# Carrier_v1_0.net
KiCad netlist of a schematic drawn in EAGLE
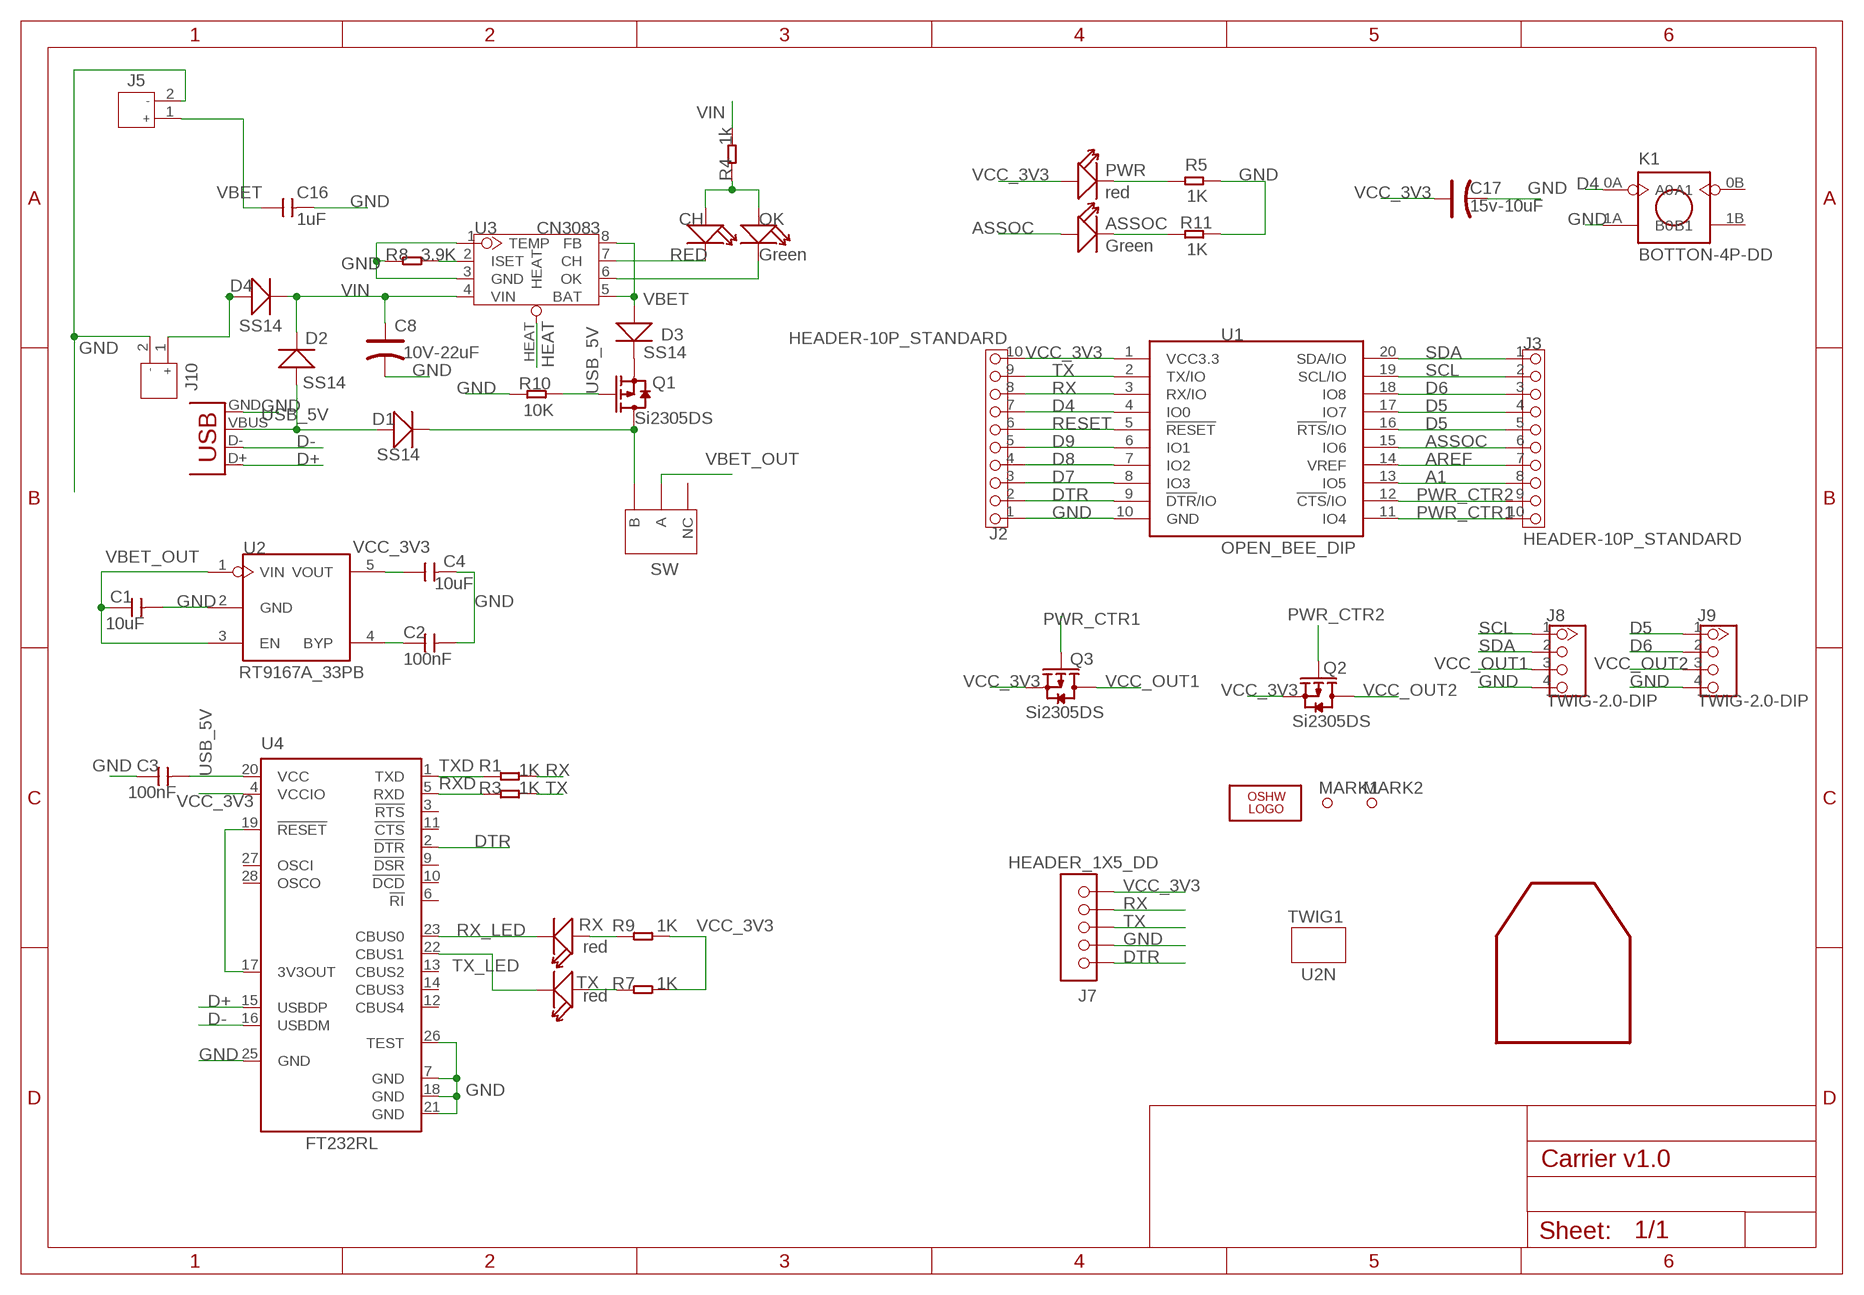
[diagram p0: schematic, sheet 1]

(export (version "E")
  (design (tool "Eeschema 10.0.6"))
  (components
    (comp (ref "ASSOC")
      (value "Green")
      (footprint "eagle-import:D0603")
      (libsource (lib "eagle-import") (part "LED-0603"))
    )
    (comp (ref "C1")
      (value "10uF")
      (footprint "eagle-import:0805")
      (libsource (lib "eagle-import") (part "C-0805"))
    )
    (comp (ref "C2")
      (value "100nF")
      (footprint "eagle-import:0603")
      (libsource (lib "eagle-import") (part "C-0603"))
    )
    (comp (ref "C3")
      (value "100nF")
      (footprint "eagle-import:0603")
      (libsource (lib "eagle-import") (part "C-0603"))
    )
    (comp (ref "C4")
      (value "10uF")
      (footprint "eagle-import:0805")
      (libsource (lib "eagle-import") (part "C-0805"))
    )
    (comp (ref "C8")
      (value "10V-22uF")
      (footprint "eagle-import:AVX-B")
      (libsource (lib "eagle-import") (part "CAP_AVX_B"))
    )
    (comp (ref "C16")
      (value "1uF")
      (footprint "eagle-import:0805")
      (libsource (lib "eagle-import") (part "C-0805"))
    )
    (comp (ref "C17")
      (value "15v-10uF")
      (footprint "eagle-import:AVX-A")
      (libsource (lib "eagle-import") (part "CAP_AVX_A"))
    )
    (comp (ref "CH")
      (value "RED")
      (footprint "eagle-import:D0603")
      (libsource (lib "eagle-import") (part "LED-0603"))
    )
    (comp (ref "D1")
      (value "SS14")
      (footprint "eagle-import:D2010")
      (libsource (lib "eagle-import") (part "D-2010"))
    )
    (comp (ref "D2")
      (value "SS14")
      (footprint "eagle-import:D2010")
      (libsource (lib "eagle-import") (part "D-2010"))
    )
    (comp (ref "D3")
      (value "SS14")
      (footprint "eagle-import:D2010")
      (libsource (lib "eagle-import") (part "D-2010"))
    )
    (comp (ref "D4")
      (value "SS14")
      (footprint "eagle-import:D2010")
      (libsource (lib "eagle-import") (part "D-2010"))
    )
    (comp (ref "J2")
      (value "HEADER-10P_STANDARD")
      (footprint "eagle-import:2.54_10P")
      (libsource (lib "eagle-import") (part "HEADER-10P_STANDARD"))
    )
    (comp (ref "J3")
      (value "HEADER-10P_STANDARD")
      (footprint "eagle-import:2.54_10P")
      (libsource (lib "eagle-import") (part "HEADER-10P_STANDARD"))
    )
    (comp (ref "J5")
      (value "JST-2P-POWER-LEADED")
      (footprint "eagle-import:2P-2.0-LEADED-4.7X6.0")
      (libsource (lib "eagle-import") (part "JST-2P-POWER-LEADED"))
    )
    (comp (ref "J7")
      (value "HEADER_1X5_DD")
      (footprint "eagle-import:CK_1X5")
      (libsource (lib "eagle-import") (part "HEADER_1X5_DD"))
    )
    (comp (ref "J8")
      (value "TWIG-2.0-DIP")
      (footprint "eagle-import:2.0_1X4")
      (libsource (lib "eagle-import") (part "TWIG-2.0-DIP"))
    )
    (comp (ref "J9")
      (value "TWIG-2.0-DIP")
      (footprint "eagle-import:2.0_1X4")
      (libsource (lib "eagle-import") (part "TWIG-2.0-DIP"))
    )
    (comp (ref "J10")
      (value "JST-2P-POWER-LEADED")
      (footprint "eagle-import:2P-2.0-LEADED-4.7X6.0")
      (libsource (lib "eagle-import") (part "JST-2P-POWER-LEADED"))
    )
    (comp (ref "K1")
      (value "BOTTON-4P-DD")
      (footprint "eagle-import:BTN-S")
      (libsource (lib "eagle-import") (part "BOTTON-4P-DD"))
    )
    (comp (ref "LOGO2")
      (value "OSHW_LOGO_FILLX0200-NT")
      (footprint "eagle-import:OSHW_FILLX200_NOTEXT")
      (libsource (lib "eagle-import") (part "OSHW_LOGO_FILLX0200-NT"))
    )
    (comp (ref "MARK1")
      (value "PAD-MARK")
      (footprint "eagle-import:MARK")
      (libsource (lib "eagle-import") (part "PAD-MARK"))
    )
    (comp (ref "MARK2")
      (value "PAD-MARK")
      (footprint "eagle-import:MARK")
      (libsource (lib "eagle-import") (part "PAD-MARK"))
    )
    (comp (ref "OK")
      (value "Green")
      (footprint "eagle-import:D0603")
      (libsource (lib "eagle-import") (part "LED-0603"))
    )
    (comp (ref "PWR")
      (value "red")
      (footprint "eagle-import:D0805")
      (libsource (lib "eagle-import") (part "LED-0805"))
    )
    (comp (ref "Q1")
      (value "Si2305DS")
      (footprint "eagle-import:SOT23")
      (libsource (lib "eagle-import") (part "010-P-MOSFETSOT23"))
    )
    (comp (ref "Q2")
      (value "Si2305DS")
      (footprint "eagle-import:SOT23")
      (libsource (lib "eagle-import") (part "010-P-MOSFETSOT23"))
    )
    (comp (ref "Q3")
      (value "Si2305DS")
      (footprint "eagle-import:SOT23")
      (libsource (lib "eagle-import") (part "010-P-MOSFETSOT23"))
    )
    (comp (ref "R1")
      (value "1K")
      (footprint "eagle-import:0603")
      (libsource (lib "eagle-import") (part "R-0603"))
    )
    (comp (ref "R3")
      (value "1K")
      (footprint "eagle-import:0603")
      (libsource (lib "eagle-import") (part "R-0603"))
    )
    (comp (ref "R4")
      (value "1k")
      (footprint "eagle-import:0603")
      (libsource (lib "eagle-import") (part "R-0603"))
    )
    (comp (ref "R5")
      (value "1K")
      (footprint "eagle-import:0603")
      (libsource (lib "eagle-import") (part "R-0603"))
    )
    (comp (ref "R7")
      (value "1K")
      (footprint "eagle-import:0603")
      (libsource (lib "eagle-import") (part "R-0603"))
    )
    (comp (ref "R8")
      (value "3.9K")
      (footprint "eagle-import:0603")
      (libsource (lib "eagle-import") (part "R-0603"))
    )
    (comp (ref "R9")
      (value "1K")
      (footprint "eagle-import:0603")
      (libsource (lib "eagle-import") (part "R-0603"))
    )
    (comp (ref "R10")
      (value "10K")
      (footprint "eagle-import:0603")
      (libsource (lib "eagle-import") (part "R-0603"))
    )
    (comp (ref "R11")
      (value "1K")
      (footprint "eagle-import:0603")
      (libsource (lib "eagle-import") (part "R-0603"))
    )
    (comp (ref "RX")
      (value "red")
      (footprint "eagle-import:D0603")
      (libsource (lib "eagle-import") (part "LED-0603"))
    )
    (comp (ref "SW")
      (value "SWITCH-3P")
      (footprint "eagle-import:008-SW-3P-DIP")
      (libsource (lib "eagle-import") (part "SWITCH-3P"))
    )
    (comp (ref "TWIG1")
      (value "U2N")
      (footprint "eagle-import:U2N_SILK")
      (libsource (lib "eagle-import") (part "U2N"))
    )
    (comp (ref "TX")
      (value "red")
      (footprint "eagle-import:D0603")
      (libsource (lib "eagle-import") (part "LED-0603"))
    )
    (comp (ref "U$1")
      (value "WIFI_SILK")
      (footprint "eagle-import:WIFI_SILK")
      (libsource (lib "eagle-import") (part "WIFI_SILK"))
    )
    (comp (ref "U1")
      (value "OPEN_BEE_DIP")
      (footprint "eagle-import:CCBEE-PRO")
      (libsource (lib "eagle-import") (part "OPEN_BEE_DIP"))
    )
    (comp (ref "U2")
      (value "RT9167A_33PB")
      (footprint "eagle-import:SOT23-5")
      (libsource (lib "eagle-import") (part "RT9167A"))
    )
    (comp (ref "U3")
      (value "CN3083")
      (footprint "eagle-import:SOP8")
      (libsource (lib "eagle-import") (part "CN3083"))
    )
    (comp (ref "U4")
      (value "FT232RL")
      (footprint "eagle-import:SSOP28")
      (libsource (lib "eagle-import") (part "FT232RL"))
    )
    (comp (ref "X1")
      (value "USB-SMD-NS")
      (footprint "eagle-import:USB-MINIB-NOSTOP")
      (libsource (lib "eagle-import") (part "USB-SMD-NS"))
    )
  )
  (nets
    (net (code "1") (name "/A1") (class "Default")
      (node (ref "J3") (pin "8") (pinfunction "8_8") (pintype "bidirectional"))
      (node (ref "U1") (pin "13") (pinfunction "IO5_13") (pintype "bidirectional"))
    )
    (net (code "2") (name "/AREF") (class "Default")
      (node (ref "J3") (pin "7") (pinfunction "7_7") (pintype "bidirectional"))
      (node (ref "U1") (pin "14") (pinfunction "VREF_14") (pintype "bidirectional"))
    )
    (net (code "3") (name "/ASSOC") (class "Default")
      (node (ref "ASSOC") (pin "+") (pinfunction "+_+") (pintype "passive"))
      (node (ref "J3") (pin "6") (pinfunction "6_6") (pintype "bidirectional"))
      (node (ref "U1") (pin "15") (pinfunction "IO6_15") (pintype "bidirectional"))
    )
    (net (code "4") (name "/D+") (class "Default")
      (node (ref "U4") (pin "15") (pinfunction "USBDP_15") (pintype "input"))
      (node (ref "X1") (pin "D+") (pinfunction "D+_D+") (pintype "bidirectional"))
    )
    (net (code "5") (name "/D-") (class "Default")
      (node (ref "U4") (pin "16") (pinfunction "USBDM_16") (pintype "input"))
      (node (ref "X1") (pin "D-") (pinfunction "D-_D-") (pintype "bidirectional"))
    )
    (net (code "6") (name "/D4") (class "Default")
      (node (ref "J2") (pin "7") (pinfunction "7_7") (pintype "bidirectional"))
      (node (ref "K1") (pin "0A") (pinfunction "A0_0A") (pintype "bidirectional"))
      (node (ref "U1") (pin "4") (pinfunction "IO0_4") (pintype "bidirectional"))
    )
    (net (code "7") (name "/D5") (class "Default")
      (node (ref "J3") (pin "4") (pinfunction "4_4") (pintype "bidirectional"))
      (node (ref "J3") (pin "5") (pinfunction "5_5") (pintype "bidirectional"))
      (node (ref "J9") (pin "1") (pinfunction "1_1") (pintype "bidirectional"))
      (node (ref "U1") (pin "16") (pinfunction "~{RTS}/IO_16") (pintype "bidirectional"))
      (node (ref "U1") (pin "17") (pinfunction "IO7_17") (pintype "bidirectional"))
    )
    (net (code "8") (name "/D6") (class "Default")
      (node (ref "J3") (pin "3") (pinfunction "3_3") (pintype "bidirectional"))
      (node (ref "J9") (pin "2") (pinfunction "2_2") (pintype "bidirectional"))
      (node (ref "U1") (pin "18") (pinfunction "IO8_18") (pintype "bidirectional"))
    )
    (net (code "9") (name "/D7") (class "Default")
      (node (ref "J2") (pin "3") (pinfunction "3_3") (pintype "bidirectional"))
      (node (ref "U1") (pin "8") (pinfunction "IO3_8") (pintype "bidirectional"))
    )
    (net (code "10") (name "/D8") (class "Default")
      (node (ref "J2") (pin "4") (pinfunction "4_4") (pintype "bidirectional"))
      (node (ref "U1") (pin "7") (pinfunction "IO2_7") (pintype "bidirectional"))
    )
    (net (code "11") (name "/D9") (class "Default")
      (node (ref "J2") (pin "5") (pinfunction "5_5") (pintype "bidirectional"))
      (node (ref "U1") (pin "6") (pinfunction "IO1_6") (pintype "bidirectional"))
    )
    (net (code "12") (name "/DTR") (class "Default")
      (node (ref "J2") (pin "2") (pinfunction "2_2") (pintype "bidirectional"))
      (node (ref "J7") (pin "1") (pinfunction "1_1") (pintype "bidirectional"))
      (node (ref "U1") (pin "9") (pinfunction "~{DTR}/IO_9") (pintype "bidirectional"))
      (node (ref "U4") (pin "2") (pinfunction "~{DTR}_2") (pintype "input"))
    )
    (net (code "13") (name "/GND") (class "Default")
      (node (ref "C1") (pin "2") (pinfunction "2_2") (pintype "passive"))
      (node (ref "C16") (pin "2") (pinfunction "2_2") (pintype "passive"))
      (node (ref "C17") (pin "-") (pinfunction "-_-") (pintype "passive"))
      (node (ref "C2") (pin "2") (pinfunction "2_2") (pintype "passive"))
      (node (ref "C3") (pin "1") (pinfunction "1_1") (pintype "passive"))
      (node (ref "C4") (pin "2") (pinfunction "2_2") (pintype "passive"))
      (node (ref "C8") (pin "-") (pinfunction "-_-") (pintype "passive"))
      (node (ref "J10") (pin "2") (pinfunction "P$2_2") (pintype "bidirectional"))
      (node (ref "J2") (pin "1") (pinfunction "1_1") (pintype "bidirectional"))
      (node (ref "J5") (pin "2") (pinfunction "P$2_2") (pintype "bidirectional"))
      (node (ref "J7") (pin "2") (pinfunction "2_2") (pintype "bidirectional"))
      (node (ref "J8") (pin "4") (pinfunction "4_4") (pintype "bidirectional"))
      (node (ref "J9") (pin "4") (pinfunction "4_4") (pintype "bidirectional"))
      (node (ref "K1") (pin "1A") (pinfunction "B0_1A") (pintype "bidirectional"))
      (node (ref "R10") (pin "1") (pinfunction "1_1") (pintype "passive"))
      (node (ref "R11") (pin "1") (pinfunction "1_1") (pintype "passive"))
      (node (ref "R5") (pin "1") (pinfunction "1_1") (pintype "passive"))
      (node (ref "R8") (pin "1") (pinfunction "1_1") (pintype "passive"))
      (node (ref "U1") (pin "10") (pinfunction "GND_10") (pintype "bidirectional"))
      (node (ref "U2") (pin "2") (pinfunction "GND_2") (pintype "bidirectional"))
      (node (ref "U3") (pin "1") (pinfunction "TEMP_1") (pintype "bidirectional"))
      (node (ref "U3") (pin "3") (pinfunction "GND_3") (pintype "bidirectional"))
      (node (ref "U4") (pin "18") (pinfunction "GND_18") (pintype "input"))
      (node (ref "U4") (pin "21") (pinfunction "GND_21") (pintype "input"))
      (node (ref "U4") (pin "25") (pinfunction "GND_25") (pintype "input"))
      (node (ref "U4") (pin "26") (pinfunction "TEST_26") (pintype "input"))
      (node (ref "U4") (pin "7") (pinfunction "GND_7") (pintype "input"))
      (node (ref "X1") (pin "GND") (pinfunction "GND_GND") (pintype "bidirectional"))
    )
    (net (code "14") (name "/HEAT") (class "Default")
      (node (ref "U3") (pin "HEAT") (pinfunction "HEAT_HEAT") (pintype "bidirectional"))
    )
    (net (code "15") (name "/PWR_CTR1") (class "Default")
      (node (ref "J3") (pin "10") (pinfunction "10_10") (pintype "bidirectional"))
      (node (ref "Q3") (pin "1") (pinfunction "G_1") (pintype "passive"))
      (node (ref "U1") (pin "11") (pinfunction "IO4_11") (pintype "bidirectional"))
    )
    (net (code "16") (name "/PWR_CTR2") (class "Default")
      (node (ref "J3") (pin "9") (pinfunction "9_9") (pintype "bidirectional"))
      (node (ref "Q2") (pin "1") (pinfunction "G_1") (pintype "passive"))
      (node (ref "U1") (pin "12") (pinfunction "~{CTS}/IO_12") (pintype "bidirectional"))
    )
    (net (code "17") (name "/RESET") (class "Default")
      (node (ref "J2") (pin "6") (pinfunction "6_6") (pintype "bidirectional"))
      (node (ref "U1") (pin "5") (pinfunction "~{RESET}_5") (pintype "bidirectional"))
    )
    (net (code "18") (name "/RX") (class "Default")
      (node (ref "J2") (pin "8") (pinfunction "8_8") (pintype "bidirectional"))
      (node (ref "J7") (pin "4") (pinfunction "4_4") (pintype "bidirectional"))
      (node (ref "R1") (pin "2") (pinfunction "2_2") (pintype "passive"))
      (node (ref "U1") (pin "3") (pinfunction "RX/IO_3") (pintype "bidirectional"))
    )
    (net (code "19") (name "/RXD") (class "Default")
      (node (ref "R3") (pin "1") (pinfunction "1_1") (pintype "passive"))
      (node (ref "U4") (pin "5") (pinfunction "RXD_5") (pintype "input"))
    )
    (net (code "20") (name "/RX_LED") (class "Default")
      (node (ref "RX") (pin "-") (pinfunction "-_-") (pintype "passive"))
      (node (ref "U4") (pin "23") (pinfunction "CBUS0_23") (pintype "input"))
    )
    (net (code "21") (name "/SCL") (class "Default")
      (node (ref "J3") (pin "2") (pinfunction "2_2") (pintype "bidirectional"))
      (node (ref "J8") (pin "1") (pinfunction "1_1") (pintype "bidirectional"))
      (node (ref "U1") (pin "19") (pinfunction "SCL/IO_19") (pintype "bidirectional"))
    )
    (net (code "22") (name "/SDA") (class "Default")
      (node (ref "J3") (pin "1") (pinfunction "1_1") (pintype "bidirectional"))
      (node (ref "J8") (pin "2") (pinfunction "2_2") (pintype "bidirectional"))
      (node (ref "U1") (pin "20") (pinfunction "SDA/IO_20") (pintype "bidirectional"))
    )
    (net (code "23") (name "/TX") (class "Default")
      (node (ref "J2") (pin "9") (pinfunction "9_9") (pintype "bidirectional"))
      (node (ref "J7") (pin "3") (pinfunction "3_3") (pintype "bidirectional"))
      (node (ref "R3") (pin "2") (pinfunction "2_2") (pintype "passive"))
      (node (ref "U1") (pin "2") (pinfunction "TX/IO_2") (pintype "bidirectional"))
    )
    (net (code "24") (name "/TXD") (class "Default")
      (node (ref "R1") (pin "1") (pinfunction "1_1") (pintype "passive"))
      (node (ref "U4") (pin "1") (pinfunction "TXD_1") (pintype "input"))
    )
    (net (code "25") (name "/TX_LED") (class "Default")
      (node (ref "TX") (pin "-") (pinfunction "-_-") (pintype "passive"))
      (node (ref "U4") (pin "22") (pinfunction "CBUS1_22") (pintype "input"))
    )
    (net (code "26") (name "/USB_5V") (class "Default")
      (node (ref "C3") (pin "2") (pinfunction "2_2") (pintype "passive"))
      (node (ref "D1") (pin "+") (pinfunction "+_+") (pintype "passive"))
      (node (ref "D2") (pin "+") (pinfunction "+_+") (pintype "passive"))
      (node (ref "Q1") (pin "1") (pinfunction "G_1") (pintype "passive"))
      (node (ref "R10") (pin "2") (pinfunction "2_2") (pintype "passive"))
      (node (ref "U4") (pin "20") (pinfunction "VCC_20") (pintype "input"))
      (node (ref "X1") (pin "VBUS") (pinfunction "VBUS_VBUS") (pintype "bidirectional"))
    )
    (net (code "27") (name "/VBET") (class "Default")
      (node (ref "C16") (pin "1") (pinfunction "1_1") (pintype "passive"))
      (node (ref "D3") (pin "+") (pinfunction "+_+") (pintype "passive"))
      (node (ref "J5") (pin "1") (pinfunction "P$1_1") (pintype "bidirectional"))
      (node (ref "U3") (pin "5") (pinfunction "BAT_5") (pintype "bidirectional"))
      (node (ref "U3") (pin "8") (pinfunction "FB_8") (pintype "bidirectional"))
    )
    (net (code "28") (name "/VBET_OUT") (class "Default")
      (node (ref "C1") (pin "1") (pinfunction "1_1") (pintype "passive"))
      (node (ref "SW") (pin "P$2") (pinfunction "A_P$2") (pintype "bidirectional"))
      (node (ref "U2") (pin "1") (pinfunction "VIN_1") (pintype "bidirectional"))
      (node (ref "U2") (pin "3") (pinfunction "EN_3") (pintype "bidirectional"))
    )
    (net (code "29") (name "/VCC_3V3") (class "Default")
      (node (ref "C17") (pin "+") (pinfunction "+_+") (pintype "passive"))
      (node (ref "C4") (pin "1") (pinfunction "1_1") (pintype "passive"))
      (node (ref "J2") (pin "10") (pinfunction "10_10") (pintype "bidirectional"))
      (node (ref "J7") (pin "5") (pinfunction "5_5") (pintype "bidirectional"))
      (node (ref "PWR") (pin "+") (pinfunction "+_+") (pintype "passive"))
      (node (ref "Q2") (pin "2") (pinfunction "S_2") (pintype "passive"))
      (node (ref "Q3") (pin "2") (pinfunction "S_2") (pintype "passive"))
      (node (ref "R7") (pin "2") (pinfunction "2_2") (pintype "passive"))
      (node (ref "R9") (pin "2") (pinfunction "2_2") (pintype "passive"))
      (node (ref "U1") (pin "1") (pinfunction "VCC3.3_1") (pintype "bidirectional"))
      (node (ref "U2") (pin "5") (pinfunction "VOUT_5") (pintype "bidirectional"))
      (node (ref "U4") (pin "4") (pinfunction "VCCIO_4") (pintype "input"))
    )
    (net (code "30") (name "/VCC_OUT1") (class "Default")
      (node (ref "J8") (pin "3") (pinfunction "3_3") (pintype "bidirectional"))
      (node (ref "Q3") (pin "3") (pinfunction "D_3") (pintype "passive"))
    )
    (net (code "31") (name "/VCC_OUT2") (class "Default")
      (node (ref "J9") (pin "3") (pinfunction "3_3") (pintype "bidirectional"))
      (node (ref "Q2") (pin "3") (pinfunction "D_3") (pintype "passive"))
    )
    (net (code "32") (name "/VIN") (class "Default")
      (node (ref "C8") (pin "+") (pinfunction "+_+") (pintype "passive"))
      (node (ref "D2") (pin "-") (pinfunction "-_-") (pintype "passive"))
      (node (ref "D4") (pin "-") (pinfunction "-_-") (pintype "passive"))
      (node (ref "R4") (pin "2") (pinfunction "2_2") (pintype "passive"))
      (node (ref "U3") (pin "4") (pinfunction "VIN_4") (pintype "bidirectional"))
    )
    (net (code "33") (name "Net-(ASSOC-Pad-)") (class "Default")
      (node (ref "ASSOC") (pin "-") (pinfunction "-_-") (pintype "passive"))
      (node (ref "R11") (pin "2") (pinfunction "2_2") (pintype "passive"))
    )
    (net (code "34") (name "Net-(CH-Pad+)") (class "Default")
      (node (ref "CH") (pin "+") (pinfunction "+_+") (pintype "passive"))
      (node (ref "OK") (pin "+") (pinfunction "+_+") (pintype "passive"))
      (node (ref "R4") (pin "1") (pinfunction "1_1") (pintype "passive"))
    )
    (net (code "35") (name "Net-(J10-P$1)") (class "Default")
      (node (ref "D4") (pin "+") (pinfunction "+_+") (pintype "passive"))
      (node (ref "J10") (pin "1") (pinfunction "P$1_1") (pintype "bidirectional"))
    )
    (net (code "36") (name "Net-(PWR-Pad-)") (class "Default")
      (node (ref "PWR") (pin "-") (pinfunction "-_-") (pintype "passive"))
      (node (ref "R5") (pin "2") (pinfunction "2_2") (pintype "passive"))
    )
    (net (code "37") (name "Net-(Q1-D)") (class "Default")
      (node (ref "D1") (pin "-") (pinfunction "-_-") (pintype "passive"))
      (node (ref "Q1") (pin "3") (pinfunction "D_3") (pintype "passive"))
      (node (ref "SW") (pin "P$3") (pinfunction "B_P$3") (pintype "bidirectional"))
    )
    (net (code "38") (name "Net-(Q1-S)") (class "Default")
      (node (ref "D3") (pin "-") (pinfunction "-_-") (pintype "passive"))
      (node (ref "Q1") (pin "2") (pinfunction "S_2") (pintype "passive"))
    )
    (net (code "39") (name "Net-(R7-Pad1)") (class "Default")
      (node (ref "R7") (pin "1") (pinfunction "1_1") (pintype "passive"))
      (node (ref "TX") (pin "+") (pinfunction "+_+") (pintype "passive"))
    )
    (net (code "40") (name "Net-(R9-Pad1)") (class "Default")
      (node (ref "R9") (pin "1") (pinfunction "1_1") (pintype "passive"))
      (node (ref "RX") (pin "+") (pinfunction "+_+") (pintype "passive"))
    )
    (net (code "41") (name "Net-(U2-BYP)") (class "Default")
      (node (ref "C2") (pin "1") (pinfunction "1_1") (pintype "passive"))
      (node (ref "U2") (pin "4") (pinfunction "BYP_4") (pintype "bidirectional"))
    )
    (net (code "42") (name "Net-(U3-CH)") (class "Default")
      (node (ref "CH") (pin "-") (pinfunction "-_-") (pintype "passive"))
      (node (ref "U3") (pin "7") (pinfunction "CH_7") (pintype "bidirectional"))
    )
    (net (code "43") (name "Net-(U3-ISET)") (class "Default")
      (node (ref "R8") (pin "2") (pinfunction "2_2") (pintype "passive"))
      (node (ref "U3") (pin "2") (pinfunction "ISET_2") (pintype "bidirectional"))
    )
    (net (code "44") (name "Net-(U3-OK)") (class "Default")
      (node (ref "OK") (pin "-") (pinfunction "-_-") (pintype "passive"))
      (node (ref "U3") (pin "6") (pinfunction "OK_6") (pintype "bidirectional"))
    )
    (net (code "45") (name "Net-(U4-3V3OUT)") (class "Default")
      (node (ref "U4") (pin "17") (pinfunction "3V3OUT_17") (pintype "input"))
      (node (ref "U4") (pin "19") (pinfunction "~{RESET}_19") (pintype "input"))
    )
    (net (code "46") (name "unconnected-(K1-A1-Pad0B)") (class "Default")
      (node (ref "K1") (pin "0B") (pinfunction "A1_0B") (pintype "bidirectional"))
    )
    (net (code "47") (name "unconnected-(K1-B1-Pad1B)") (class "Default")
      (node (ref "K1") (pin "1B") (pinfunction "B1_1B") (pintype "bidirectional"))
    )
    (net (code "48") (name "unconnected-(SW-NC-PadP$1)") (class "Default")
      (node (ref "SW") (pin "P$1") (pinfunction "NC_P$1") (pintype "no_connect"))
    )
    (net (code "49") (name "unconnected-(U4-CBUS2-Pad13)") (class "Default")
      (node (ref "U4") (pin "13") (pinfunction "CBUS2_13") (pintype "input"))
    )
    (net (code "50") (name "unconnected-(U4-CBUS3-Pad14)") (class "Default")
      (node (ref "U4") (pin "14") (pinfunction "CBUS3_14") (pintype "input"))
    )
    (net (code "51") (name "unconnected-(U4-CBUS4-Pad12)") (class "Default")
      (node (ref "U4") (pin "12") (pinfunction "CBUS4_12") (pintype "input"))
    )
    (net (code "52") (name "unconnected-(U4-OSCI-Pad27)") (class "Default")
      (node (ref "U4") (pin "27") (pinfunction "OSCI_27") (pintype "input"))
    )
    (net (code "53") (name "unconnected-(U4-OSCO-Pad28)") (class "Default")
      (node (ref "U4") (pin "28") (pinfunction "OSCO_28") (pintype "input"))
    )
    (net (code "54") (name "unconnected-(U4-~{CTS}-Pad11)") (class "Default")
      (node (ref "U4") (pin "11") (pinfunction "~{CTS}_11") (pintype "input"))
    )
    (net (code "55") (name "unconnected-(U4-~{DCD}-Pad10)") (class "Default")
      (node (ref "U4") (pin "10") (pinfunction "~{DCD}_10") (pintype "input"))
    )
    (net (code "56") (name "unconnected-(U4-~{DSR}-Pad9)") (class "Default")
      (node (ref "U4") (pin "9") (pinfunction "~{DSR}_9") (pintype "input"))
    )
    (net (code "57") (name "unconnected-(U4-~{RI}-Pad6)") (class "Default")
      (node (ref "U4") (pin "6") (pinfunction "~{RI}_6") (pintype "input"))
    )
    (net (code "58") (name "unconnected-(U4-~{RTS}-Pad3)") (class "Default")
      (node (ref "U4") (pin "3") (pinfunction "~{RTS}_3") (pintype "input"))
    )
  )
)
